# cpu-driver.net
KiCad netlist of a schematic drawn in EAGLE
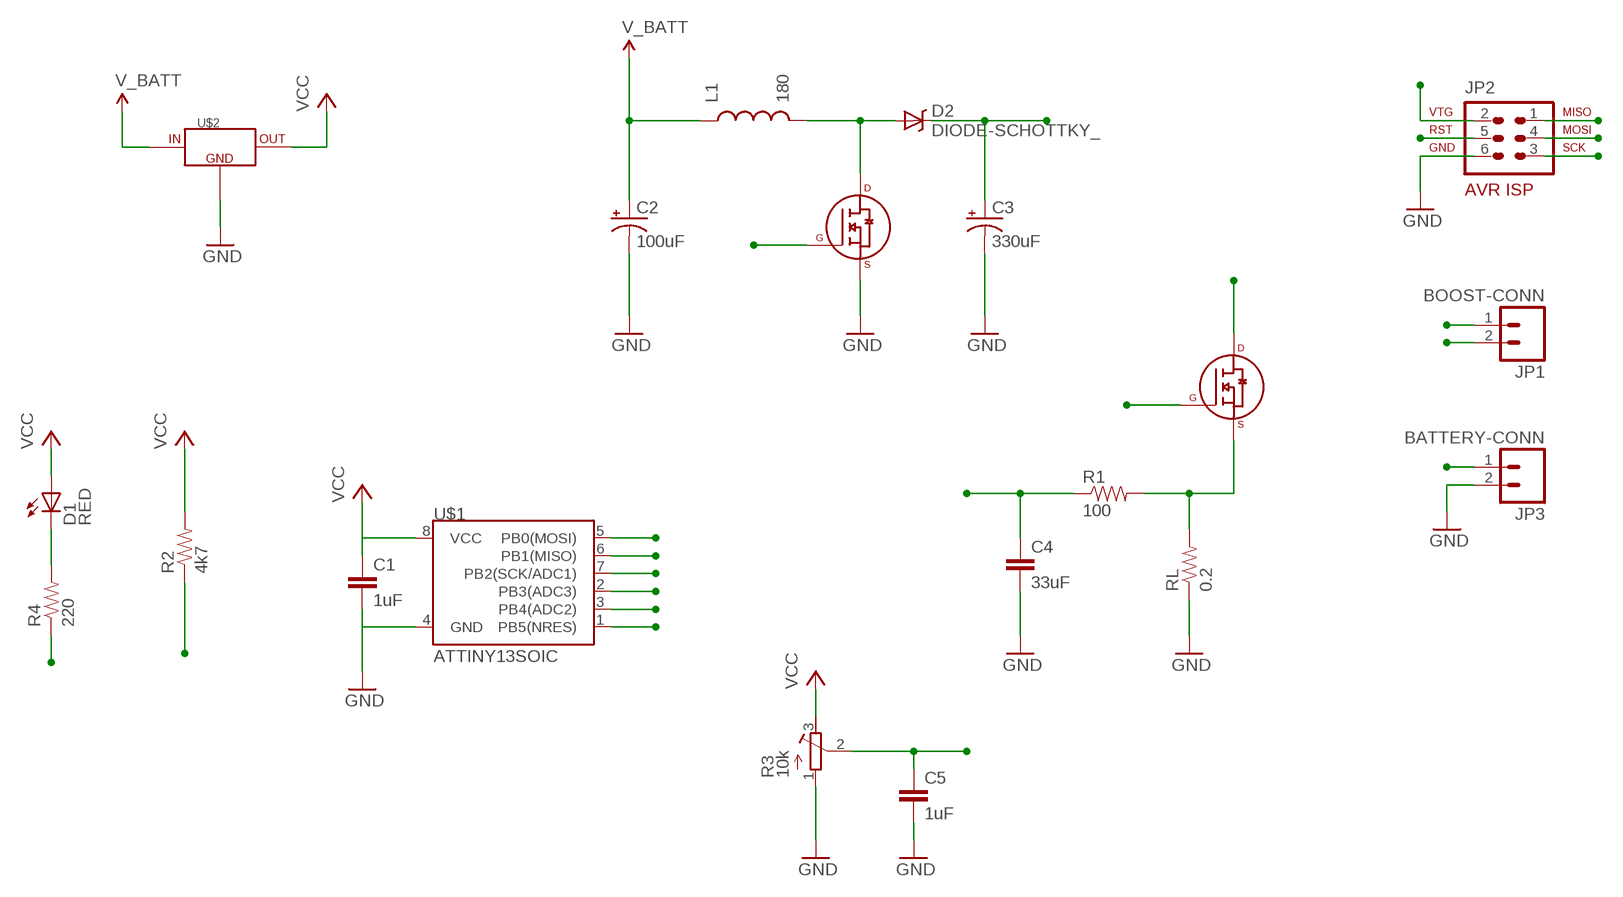
[diagram p0: schematic, sheet 1]

(export (version "E")
  (design (tool "Eeschema 10.0.6"))
  (components
    (comp (ref "C1")
      (value "1uF")
      (footprint "eagle-import:0603-CAP")
      (libsource (lib "eagle-import") (part "CAP0603-CAP"))
    )
    (comp (ref "C2")
      (value "100uF")
      (footprint "eagle-import:PANASONIC_D")
      (libsource (lib "eagle-import") (part "CPOL-USD"))
    )
    (comp (ref "C3")
      (value "330uF")
      (footprint "eagle-import:PANASONIC_D")
      (libsource (lib "eagle-import") (part "CPOL-USD"))
    )
    (comp (ref "C4")
      (value "33uF")
      (footprint "eagle-import:0603-CAP")
      (libsource (lib "eagle-import") (part "CAP0603-CAP"))
    )
    (comp (ref "C5")
      (value "1uF")
      (footprint "eagle-import:0603-CAP")
      (libsource (lib "eagle-import") (part "CAP0603-CAP"))
    )
    (comp (ref "D1")
      (value "RED")
      (footprint "eagle-import:LED-0603")
      (libsource (lib "eagle-import") (part "LED-RED0603"))
    )
    (comp (ref "D2")
      (value "DIODE-SCHOTTKY_")
      (footprint "eagle-import:SMA-DIODE")
      (libsource (lib "eagle-import") (part "DIODE-SCHOTTKY_"))
    )
    (comp (ref "JP1")
      (value "BOOST-CONN")
      (footprint "eagle-import:1X02_LOCK_LONGPADS")
      (libsource (lib "eagle-import") (part "M02LOCK_LONGPADS"))
    )
    (comp (ref "JP2")
      (value "AVR-ISP-6")
      (footprint "eagle-import:AVR-ISP-6")
      (libsource (lib "eagle-import") (part "AVR-ISP-6"))
    )
    (comp (ref "JP3")
      (value "BATTERY-CONN")
      (footprint "eagle-import:1X02_LOCK_LONGPADS")
      (libsource (lib "eagle-import") (part "M02LOCK_LONGPADS"))
    )
    (comp (ref "L1")
      (value "180")
      (footprint "eagle-import:DR1030")
      (libsource (lib "eagle-import") (part "INDUCTORDR1030"))
    )
    (comp (ref "Q1")
      (value "RFD14N05L")
      (footprint "eagle-import:TO-252AA")
      (libsource (lib "eagle-import") (part "RFD14N05L"))
    )
    (comp (ref "Q2")
      (value "RFD14N05L")
      (footprint "eagle-import:TO-252AA")
      (libsource (lib "eagle-import") (part "RFD14N05L"))
    )
    (comp (ref "R1")
      (value "100")
      (footprint "eagle-import:0603-RES")
      (libsource (lib "eagle-import") (part "RESISTOR0603-RES"))
    )
    (comp (ref "R2")
      (value "4k7")
      (footprint "eagle-import:0603-RES")
      (libsource (lib "eagle-import") (part "RESISTOR0603-RES"))
    )
    (comp (ref "R3")
      (value "10k")
      (footprint "eagle-import:RTRIM64Y")
      (libsource (lib "eagle-import") (part "R-TRIMM64Y"))
    )
    (comp (ref "R4")
      (value "220")
      (footprint "eagle-import:0603-RES")
      (libsource (lib "eagle-import") (part "RESISTOR0603-RES"))
    )
    (comp (ref "RL")
      (value "0.2")
      (footprint "eagle-import:R2512")
      (libsource (lib "eagle-import") (part "RESISTOR2512"))
    )
    (comp (ref "U$1")
      (value "ATTINY13SOIC")
      (footprint "eagle-import:SO08")
      (libsource (lib "eagle-import") (part "ATTINY13SOIC"))
    )
    (comp (ref "U$2")
      (value "TPS715XX")
      (footprint "eagle-import:SOT-23-5")
      (libsource (lib "eagle-import") (part "TPS715XX"))
    )
  )
  (nets
    (net (code "1") (name "/BOOST+") (class "Default")
      (node (ref "C3") (pin "+") (pinfunction "+_+") (pintype "passive"))
      (node (ref "D2") (pin "C") (pinfunction "C_C") (pintype "passive"))
      (node (ref "JP1") (pin "1") (pinfunction "1_1") (pintype "passive"))
    )
    (net (code "2") (name "/BOOST-") (class "Default")
      (node (ref "JP1") (pin "2") (pinfunction "2_2") (pintype "passive"))
      (node (ref "Q2") (pin "4") (pinfunction "D_4") (pintype "bidirectional"))
    )
    (net (code "3") (name "/MISO") (class "Default")
      (node (ref "JP2") (pin "1") (pinfunction "1_1") (pintype "passive"))
      (node (ref "Q1") (pin "1") (pinfunction "G_1") (pintype "bidirectional"))
      (node (ref "U$1") (pin "6") (pinfunction "PB1(MISO)_6") (pintype "bidirectional"))
    )
    (net (code "4") (name "/MOSI") (class "Default")
      (node (ref "JP2") (pin "4") (pinfunction "4_4") (pintype "passive"))
      (node (ref "R4") (pin "1") (pinfunction "1_1") (pintype "passive"))
      (node (ref "U$1") (pin "5") (pinfunction "PB0(MOSI)_5") (pintype "bidirectional"))
    )
    (net (code "5") (name "/PB3") (class "Default")
      (node (ref "C5") (pin "1") (pinfunction "1_1") (pintype "passive"))
      (node (ref "R3") (pin "2") (pinfunction "S_2") (pintype "passive"))
      (node (ref "U$1") (pin "2") (pinfunction "PB3(ADC3)_2") (pintype "bidirectional"))
    )
    (net (code "6") (name "/PB4") (class "Default")
      (node (ref "C4") (pin "1") (pinfunction "1_1") (pintype "passive"))
      (node (ref "R1") (pin "1") (pinfunction "1_1") (pintype "passive"))
      (node (ref "U$1") (pin "3") (pinfunction "PB4(ADC2)_3") (pintype "bidirectional"))
    )
    (net (code "7") (name "/RES") (class "Default")
      (node (ref "JP2") (pin "5") (pinfunction "5_5") (pintype "passive"))
      (node (ref "R2") (pin "1") (pinfunction "1_1") (pintype "passive"))
      (node (ref "U$1") (pin "1") (pinfunction "PB5(NRES)_1") (pintype "bidirectional"))
    )
    (net (code "8") (name "/SCK") (class "Default")
      (node (ref "JP2") (pin "3") (pinfunction "3_3") (pintype "passive"))
      (node (ref "Q2") (pin "1") (pinfunction "G_1") (pintype "bidirectional"))
      (node (ref "U$1") (pin "7") (pinfunction "PB2(SCK/ADC1)_7") (pintype "bidirectional"))
    )
    (net (code "9") (name "GND") (class "Default")
      (node (ref "C1") (pin "2") (pinfunction "2_2") (pintype "passive"))
      (node (ref "C2") (pin "-") (pinfunction "-_-") (pintype "passive"))
      (node (ref "C3") (pin "-") (pinfunction "-_-") (pintype "passive"))
      (node (ref "C4") (pin "2") (pinfunction "2_2") (pintype "passive"))
      (node (ref "C5") (pin "2") (pinfunction "2_2") (pintype "passive"))
      (node (ref "JP2") (pin "6") (pinfunction "6_6") (pintype "passive"))
      (node (ref "JP3") (pin "2") (pinfunction "2_2") (pintype "passive"))
      (node (ref "Q1") (pin "3") (pinfunction "S_3") (pintype "bidirectional"))
      (node (ref "R3") (pin "1") (pinfunction "E_1") (pintype "passive"))
      (node (ref "RL") (pin "1") (pinfunction "1_1") (pintype "passive"))
      (node (ref "U$1") (pin "4") (pinfunction "GND_4") (pintype "bidirectional"))
      (node (ref "U$2") (pin "2") (pinfunction "GND_2") (pintype "bidirectional"))
    )
    (net (code "10") (name "Net-(D1-PadC)") (class "Default")
      (node (ref "D1") (pin "C") (pinfunction "C_C") (pintype "passive"))
      (node (ref "R4") (pin "2") (pinfunction "2_2") (pintype "passive"))
    )
    (net (code "11") (name "Net-(Q1-D)") (class "Default")
      (node (ref "D2") (pin "A") (pinfunction "A_A") (pintype "passive"))
      (node (ref "L1") (pin "2") (pinfunction "2_2") (pintype "passive"))
      (node (ref "Q1") (pin "4") (pinfunction "D_4") (pintype "bidirectional"))
    )
    (net (code "12") (name "Net-(Q2-S)") (class "Default")
      (node (ref "Q2") (pin "3") (pinfunction "S_3") (pintype "bidirectional"))
      (node (ref "R1") (pin "2") (pinfunction "2_2") (pintype "passive"))
      (node (ref "RL") (pin "2") (pinfunction "2_2") (pintype "passive"))
    )
    (net (code "13") (name "VCC") (class "Default")
      (node (ref "C1") (pin "1") (pinfunction "1_1") (pintype "passive"))
      (node (ref "D1") (pin "A") (pinfunction "A_A") (pintype "passive"))
      (node (ref "R2") (pin "2") (pinfunction "2_2") (pintype "passive"))
      (node (ref "R3") (pin "3") (pinfunction "A_3") (pintype "passive"))
      (node (ref "U$1") (pin "8") (pinfunction "VCC_8") (pintype "bidirectional"))
      (node (ref "U$2") (pin "5") (pinfunction "OUT_5") (pintype "bidirectional"))
    )
    (net (code "14") (name "V_BATT") (class "Default")
      (node (ref "C2") (pin "+") (pinfunction "+_+") (pintype "passive"))
      (node (ref "JP3") (pin "1") (pinfunction "1_1") (pintype "passive"))
      (node (ref "L1") (pin "1") (pinfunction "1_1") (pintype "passive"))
      (node (ref "U$2") (pin "4") (pinfunction "IN_4") (pintype "bidirectional"))
    )
    (net (code "15") (name "unconnected-(JP2-Pad2)") (class "Default")
      (node (ref "JP2") (pin "2") (pinfunction "2_2") (pintype "passive"))
    )
  )
)
